# RFID_dongle.net
KiCad netlist of a schematic drawn in EAGLE
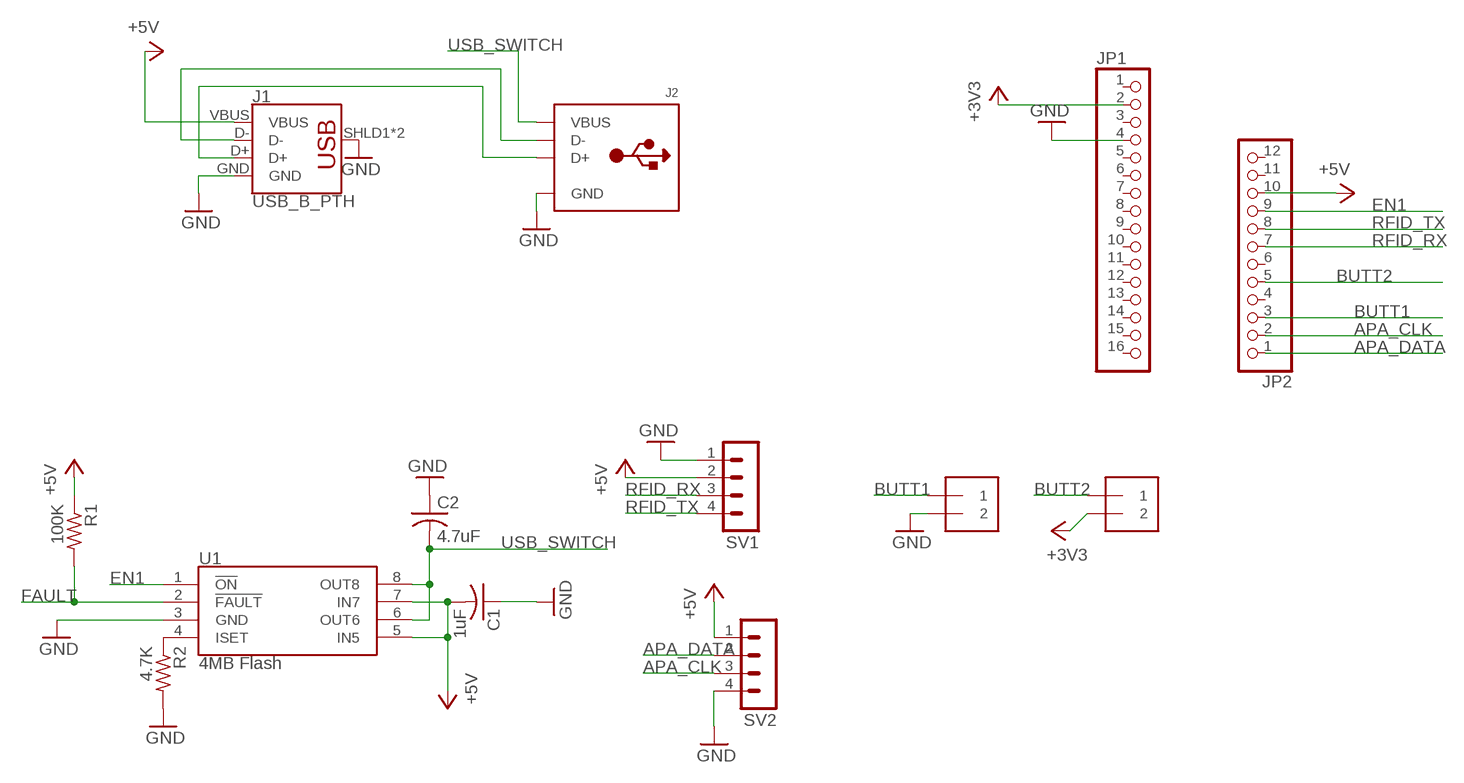
[diagram p0: schematic, sheet 1]

(export (version "E")
  (design (tool "Eeschema 10.0.6"))
  (components
    (comp (ref "C1")
      (value "1uF")
      (footprint "eagle-import:C0805K")
      (libsource (lib "eagle-import") (part "C-USC0805K"))
    )
    (comp (ref "C2")
      (value "4.7uF")
      (footprint "eagle-import:C0805K")
      (libsource (lib "eagle-import") (part "C-USC0805K"))
    )
    (comp (ref "J1")
      (value "USB_B_PTH")
      (footprint "eagle-import:USB-B-PTH")
      (libsource (lib "eagle-import") (part "USB_B_PTH"))
    )
    (comp (ref "J2")
      (value "USB_TYPEAPTHFML")
      (footprint "eagle-import:USB_HOST-PTH")
      (libsource (lib "eagle-import") (part "USB_TYPEAPTHFML"))
    )
    (comp (ref "J5")
      (value "1X2-3.5MM")
      (footprint "eagle-import:1X2-3.5MM")
      (libsource (lib "eagle-import") (part "1X2-3.5MM"))
    )
    (comp (ref "J6")
      (value "1X2-3.5MM")
      (footprint "eagle-import:1X2-3.5MM")
      (libsource (lib "eagle-import") (part "1X2-3.5MM"))
    )
    (comp (ref "JP1")
      (value "HEADER-1X16_MIN")
      (footprint "eagle-import:1X16_ROUND_MIN")
      (libsource (lib "eagle-import") (part "HEADER-1X16_MIN"))
    )
    (comp (ref "JP2")
      (value "HEADER-1X12_MIN")
      (footprint "eagle-import:1X12_ROUND_MIN")
      (libsource (lib "eagle-import") (part "HEADER-1X12_MIN"))
    )
    (comp (ref "R1")
      (value "100K")
      (footprint "eagle-import:R0805")
      (libsource (lib "eagle-import") (part "R-US_R0805"))
    )
    (comp (ref "R2")
      (value "4.7K")
      (footprint "eagle-import:R0805")
      (libsource (lib "eagle-import") (part "R-US_R0805"))
    )
    (comp (ref "SV1")
      (value "MA04-1")
      (footprint "eagle-import:MA04-1")
      (libsource (lib "eagle-import") (part "MA04-1"))
    )
    (comp (ref "SV2")
      (value "MA04-1")
      (footprint "eagle-import:MA04-1")
      (libsource (lib "eagle-import") (part "MA04-1"))
    )
    (comp (ref "U1")
      (value "4MB Flash")
      (footprint "eagle-import:SO08")
      (libsource (lib "eagle-import") (part "AT25SF041"))
    )
  )
  (nets
    (net (code "1") (name "+3V3") (class "Default")
      (node (ref "J6") (pin "2") (pinfunction "2_2") (pintype "passive"))
      (node (ref "JP1") (pin "2") (pinfunction "2_2") (pintype "passive"))
    )
    (net (code "2") (name "+5V") (class "Default")
      (node (ref "C1") (pin "2") (pinfunction "2_2") (pintype "passive"))
      (node (ref "J1") (pin "VBUS") (pinfunction "VBUS_VBUS") (pintype "power_in"))
      (node (ref "JP2") (pin "10") (pinfunction "10_10") (pintype "passive"))
      (node (ref "R1") (pin "1") (pinfunction "1_1") (pintype "passive"))
      (node (ref "SV1") (pin "2") (pinfunction "2_2") (pintype "passive"))
      (node (ref "SV2") (pin "1") (pinfunction "1_1") (pintype "passive"))
      (node (ref "U1") (pin "5") (pinfunction "IN5_5") (pintype "bidirectional"))
      (node (ref "U1") (pin "7") (pinfunction "IN7_7") (pintype "bidirectional"))
    )
    (net (code "3") (name "/APA_CLK") (class "Default")
      (node (ref "JP2") (pin "2") (pinfunction "2_2") (pintype "passive"))
      (node (ref "SV2") (pin "3") (pinfunction "3_3") (pintype "passive"))
    )
    (net (code "4") (name "/APA_DATA") (class "Default")
      (node (ref "JP2") (pin "1") (pinfunction "1_1") (pintype "passive"))
      (node (ref "SV2") (pin "2") (pinfunction "2_2") (pintype "passive"))
    )
    (net (code "5") (name "/BUTT1") (class "Default")
      (node (ref "J5") (pin "1") (pinfunction "1_1") (pintype "passive"))
      (node (ref "JP2") (pin "3") (pinfunction "3_3") (pintype "passive"))
    )
    (net (code "6") (name "/BUTT2") (class "Default")
      (node (ref "J6") (pin "1") (pinfunction "1_1") (pintype "passive"))
      (node (ref "JP2") (pin "5") (pinfunction "5_5") (pintype "passive"))
    )
    (net (code "7") (name "/EN1") (class "Default")
      (node (ref "JP2") (pin "9") (pinfunction "9_9") (pintype "passive"))
      (node (ref "U1") (pin "1") (pinfunction "~{ON}_1") (pintype "bidirectional"))
    )
    (net (code "8") (name "/FAULT") (class "Default")
      (node (ref "R1") (pin "2") (pinfunction "2_2") (pintype "passive"))
      (node (ref "U1") (pin "2") (pinfunction "~{FAULT}_2") (pintype "bidirectional"))
    )
    (net (code "9") (name "/RFID_RX") (class "Default")
      (node (ref "JP2") (pin "7") (pinfunction "7_7") (pintype "passive"))
      (node (ref "SV1") (pin "3") (pinfunction "3_3") (pintype "passive"))
    )
    (net (code "10") (name "/RFID_TX") (class "Default")
      (node (ref "JP2") (pin "8") (pinfunction "8_8") (pintype "passive"))
      (node (ref "SV1") (pin "4") (pinfunction "4_4") (pintype "passive"))
    )
    (net (code "11") (name "/USB_SWITCH") (class "Default")
      (node (ref "C2") (pin "2") (pinfunction "2_2") (pintype "passive"))
      (node (ref "J2") (pin "VBUS") (pinfunction "VBUS_VBUS") (pintype "power_in"))
      (node (ref "U1") (pin "6") (pinfunction "OUT6_6") (pintype "bidirectional"))
      (node (ref "U1") (pin "8") (pinfunction "OUT8_8") (pintype "bidirectional"))
    )
    (net (code "12") (name "GND") (class "Default")
      (node (ref "C1") (pin "1") (pinfunction "1_1") (pintype "passive"))
      (node (ref "C2") (pin "1") (pinfunction "1_1") (pintype "passive"))
      (node (ref "J1") (pin "GND") (pinfunction "GND_GND") (pintype "power_in"))
      (node (ref "J1") (pin "SHLD1") (pinfunction "SHIELD_SHLD1") (pintype "bidirectional"))
      (node (ref "J1") (pin "SHLD2") (pinfunction "SHIELD_SHLD2") (pintype "bidirectional"))
      (node (ref "J2") (pin "GND") (pinfunction "GND_GND") (pintype "power_in"))
      (node (ref "J2") (pin "S1") (pinfunction "GND_S1") (pintype "power_in"))
      (node (ref "J2") (pin "S2") (pinfunction "GND_S2") (pintype "power_in"))
      (node (ref "J5") (pin "2") (pinfunction "2_2") (pintype "passive"))
      (node (ref "JP1") (pin "4") (pinfunction "4_4") (pintype "passive"))
      (node (ref "R2") (pin "2") (pinfunction "2_2") (pintype "passive"))
      (node (ref "SV1") (pin "1") (pinfunction "1_1") (pintype "passive"))
      (node (ref "SV2") (pin "4") (pinfunction "4_4") (pintype "passive"))
      (node (ref "U1") (pin "3") (pinfunction "GND_3") (pintype "bidirectional"))
    )
    (net (code "13") (name "Net-(J1-PadD+)") (class "Default")
      (node (ref "J1") (pin "D+") (pinfunction "D+_D+") (pintype "bidirectional"))
      (node (ref "J2") (pin "D+") (pinfunction "D+_D+") (pintype "bidirectional"))
    )
    (net (code "14") (name "Net-(J1-PadD-)") (class "Default")
      (node (ref "J1") (pin "D-") (pinfunction "D-_D-") (pintype "bidirectional"))
      (node (ref "J2") (pin "D-") (pinfunction "D-_D-") (pintype "bidirectional"))
    )
    (net (code "15") (name "Net-(U1-ISET)") (class "Default")
      (node (ref "R2") (pin "1") (pinfunction "1_1") (pintype "passive"))
      (node (ref "U1") (pin "4") (pinfunction "ISET_4") (pintype "bidirectional"))
    )
    (net (code "16") (name "unconnected-(JP1-Pad1)") (class "Default")
      (node (ref "JP1") (pin "1") (pinfunction "1_1") (pintype "passive"))
    )
    (net (code "17") (name "unconnected-(JP1-Pad3)") (class "Default")
      (node (ref "JP1") (pin "3") (pinfunction "3_3") (pintype "passive"))
    )
    (net (code "18") (name "unconnected-(JP1-Pad5)") (class "Default")
      (node (ref "JP1") (pin "5") (pinfunction "5_5") (pintype "passive"))
    )
    (net (code "19") (name "unconnected-(JP1-Pad6)") (class "Default")
      (node (ref "JP1") (pin "6") (pinfunction "6_6") (pintype "passive"))
    )
    (net (code "20") (name "unconnected-(JP1-Pad7)") (class "Default")
      (node (ref "JP1") (pin "7") (pinfunction "7_7") (pintype "passive"))
    )
    (net (code "21") (name "unconnected-(JP1-Pad8)") (class "Default")
      (node (ref "JP1") (pin "8") (pinfunction "8_8") (pintype "passive"))
    )
    (net (code "22") (name "unconnected-(JP1-Pad9)") (class "Default")
      (node (ref "JP1") (pin "9") (pinfunction "9_9") (pintype "passive"))
    )
    (net (code "23") (name "unconnected-(JP1-Pad10)") (class "Default")
      (node (ref "JP1") (pin "10") (pinfunction "10_10") (pintype "passive"))
    )
    (net (code "24") (name "unconnected-(JP1-Pad11)") (class "Default")
      (node (ref "JP1") (pin "11") (pinfunction "11_11") (pintype "passive"))
    )
    (net (code "25") (name "unconnected-(JP1-Pad12)") (class "Default")
      (node (ref "JP1") (pin "12") (pinfunction "12_12") (pintype "passive"))
    )
    (net (code "26") (name "unconnected-(JP1-Pad13)") (class "Default")
      (node (ref "JP1") (pin "13") (pinfunction "13_13") (pintype "passive"))
    )
    (net (code "27") (name "unconnected-(JP1-Pad14)") (class "Default")
      (node (ref "JP1") (pin "14") (pinfunction "14_14") (pintype "passive"))
    )
    (net (code "28") (name "unconnected-(JP1-Pad15)") (class "Default")
      (node (ref "JP1") (pin "15") (pinfunction "15_15") (pintype "passive"))
    )
    (net (code "29") (name "unconnected-(JP1-Pad16)") (class "Default")
      (node (ref "JP1") (pin "16") (pinfunction "16_16") (pintype "passive"))
    )
    (net (code "30") (name "unconnected-(JP2-Pad4)") (class "Default")
      (node (ref "JP2") (pin "4") (pinfunction "4_4") (pintype "passive"))
    )
    (net (code "31") (name "unconnected-(JP2-Pad6)") (class "Default")
      (node (ref "JP2") (pin "6") (pinfunction "6_6") (pintype "passive"))
    )
    (net (code "32") (name "unconnected-(JP2-Pad11)") (class "Default")
      (node (ref "JP2") (pin "11") (pinfunction "11_11") (pintype "passive"))
    )
    (net (code "33") (name "unconnected-(JP2-Pad12)") (class "Default")
      (node (ref "JP2") (pin "12") (pinfunction "12_12") (pintype "passive"))
    )
  )
)
